# RS485.net
KiCad netlist of a schematic drawn in Altium Designer
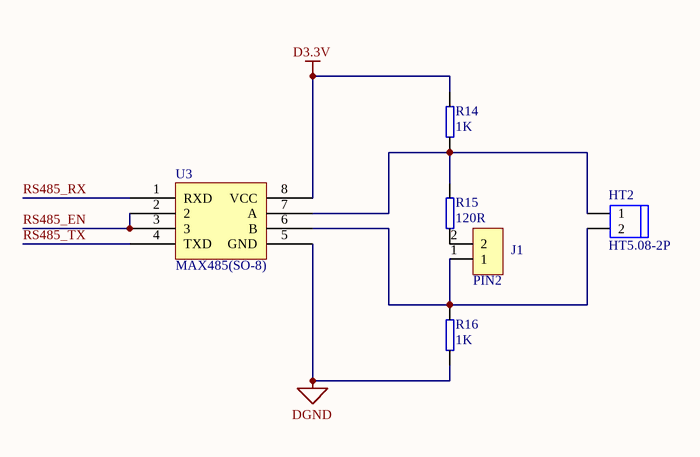
[diagram p0: RS485.SchDoc]

(export (version "E")
  (design (tool "Eeschema 10.0.6"))
  (components
    (comp (ref "HT2")
      (value "HT5.08-2P")
      (footprint "HEAD2-5.08")
      (description "5.08蓝色接口座子")
      (libsource (lib "接口") (part "HT5.08-2P"))
    )
    (comp (ref "J1") (value "PIN2") (footprint "PIN2-2.54") (libsource (lib "接口") (part "PIN2")))
    (comp (ref "R14") (value "1K") (footprint "0805-RES") (libsource (lib "常用元件") (part "RES-1K")))
    (comp (ref "R15") (value "120R") (footprint "0805-RES") (libsource (lib "常用元件") (part "RES-1K")))
    (comp (ref "R16") (value "1K") (footprint "0805-RES") (libsource (lib "常用元件") (part "RES-1K")))
    (comp (ref "U3") (value "MAX485(SO-8)") (footprint "SOP8") (libsource (lib "常用元件") (part "MAX485(SO-8)")))
  )
  (nets
    (net (code "1") (name "/RS485_EN") (class "Default")
      (node (ref "U3") (pin "2") (pinfunction "2_2") (pintype "passive"))
      (node (ref "U3") (pin "3") (pinfunction "3_3") (pintype "passive"))
    )
    (net (code "2") (name "/RS485_RX") (class "Default")
      (node (ref "U3") (pin "1") (pinfunction "RXD_1") (pintype "passive"))
    )
    (net (code "3") (name "/RS485_TX") (class "Default")
      (node (ref "U3") (pin "4") (pinfunction "TXD_4") (pintype "passive"))
    )
    (net (code "4") (name "D3.3V") (class "Default")
      (node (ref "R14") (pin "2") (pintype "passive"))
      (node (ref "U3") (pin "8") (pinfunction "VCC_8") (pintype "passive"))
    )
    (net (code "5") (name "DGND") (class "Default")
      (node (ref "R16") (pin "1") (pintype "passive"))
      (node (ref "U3") (pin "5") (pinfunction "GND_5") (pintype "passive"))
    )
    (net (code "6") (name "Net-(J1-Pad2)") (class "Default")
      (node (ref "J1") (pin "2") (pinfunction "2_2") (pintype "passive"))
      (node (ref "R15") (pin "1") (pintype "passive"))
    )
    (net (code "7") (name "Net-(U3-A)") (class "Default")
      (node (ref "HT2") (pin "1") (pinfunction "1_1") (pintype "passive"))
      (node (ref "R14") (pin "1") (pintype "passive"))
      (node (ref "R15") (pin "2") (pintype "passive"))
      (node (ref "U3") (pin "7") (pinfunction "A_7") (pintype "passive"))
    )
    (net (code "8") (name "Net-(U3-B)") (class "Default")
      (node (ref "HT2") (pin "2") (pinfunction "2_2") (pintype "passive"))
      (node (ref "J1") (pin "1") (pinfunction "1_1") (pintype "passive"))
      (node (ref "R16") (pin "2") (pintype "passive"))
      (node (ref "U3") (pin "6") (pinfunction "B_6") (pintype "passive"))
    )
  )
)
